# one-stage-full-wave-cockcroft-walton.net
KiCad netlist of a schematic drawn in EAGLE
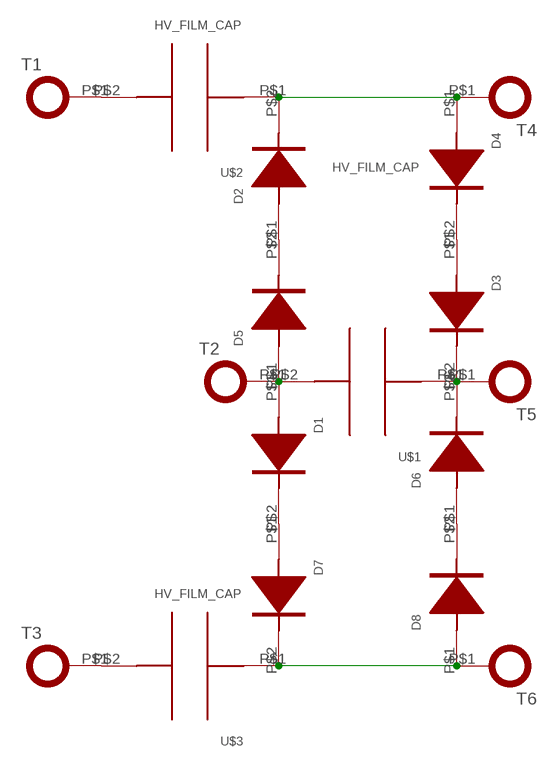
[diagram p0: schematic, sheet 1]

(export (version "E")
  (design (tool "Eeschema 10.0.6"))
  (components
    (comp (ref "D1")
      (value "DIODE_14MM")
      (footprint "eagle-import:DIODE_14")
      (libsource (lib "eagle-import") (part "DIODE_14MM"))
    )
    (comp (ref "D2")
      (value "DIODE_14MM")
      (footprint "eagle-import:DIODE_14")
      (libsource (lib "eagle-import") (part "DIODE_14MM"))
    )
    (comp (ref "D3")
      (value "DIODE_14MM")
      (footprint "eagle-import:DIODE_14")
      (libsource (lib "eagle-import") (part "DIODE_14MM"))
    )
    (comp (ref "D4")
      (value "DIODE_14MM")
      (footprint "eagle-import:DIODE_14")
      (libsource (lib "eagle-import") (part "DIODE_14MM"))
    )
    (comp (ref "D5")
      (value "DIODE_14MM")
      (footprint "eagle-import:DIODE_14")
      (libsource (lib "eagle-import") (part "DIODE_14MM"))
    )
    (comp (ref "D6")
      (value "DIODE_14MM")
      (footprint "eagle-import:DIODE_14")
      (libsource (lib "eagle-import") (part "DIODE_14MM"))
    )
    (comp (ref "D7")
      (value "DIODE_14MM")
      (footprint "eagle-import:DIODE_14")
      (libsource (lib "eagle-import") (part "DIODE_14MM"))
    )
    (comp (ref "D8")
      (value "DIODE_14MM")
      (footprint "eagle-import:DIODE_14")
      (libsource (lib "eagle-import") (part "DIODE_14MM"))
    )
    (comp (ref "T1")
      (value "TERMINAL_M6")
      (footprint "eagle-import:LUG_SQUARE_M6")
      (libsource (lib "eagle-import") (part "TERMINAL_M6"))
    )
    (comp (ref "T2")
      (value "TERMINAL_M6")
      (footprint "eagle-import:LUG_SQUARE_M6")
      (libsource (lib "eagle-import") (part "TERMINAL_M6"))
    )
    (comp (ref "T3")
      (value "TERMINAL_M6")
      (footprint "eagle-import:LUG_SQUARE_M6")
      (libsource (lib "eagle-import") (part "TERMINAL_M6"))
    )
    (comp (ref "T4")
      (value "TERMINAL_M6")
      (footprint "eagle-import:LUG_SQUARE_M6")
      (libsource (lib "eagle-import") (part "TERMINAL_M6"))
    )
    (comp (ref "T5")
      (value "TERMINAL_M6")
      (footprint "eagle-import:LUG_SQUARE_M6")
      (libsource (lib "eagle-import") (part "TERMINAL_M6"))
    )
    (comp (ref "T6")
      (value "TERMINAL_M6")
      (footprint "eagle-import:LUG_SQUARE_M6")
      (libsource (lib "eagle-import") (part "TERMINAL_M6"))
    )
    (comp (ref "U$1")
      (value "HV_FILM_CAP")
      (footprint "eagle-import:HV_FILM_CAP")
      (libsource (lib "eagle-import") (part "HV_FILM_CAP"))
    )
    (comp (ref "U$2")
      (value "HV_FILM_CAP")
      (footprint "eagle-import:HV_FILM_CAP")
      (libsource (lib "eagle-import") (part "HV_FILM_CAP"))
    )
    (comp (ref "U$3")
      (value "HV_FILM_CAP")
      (footprint "eagle-import:HV_FILM_CAP")
      (libsource (lib "eagle-import") (part "HV_FILM_CAP"))
    )
  )
  (nets
    (net (code "1") (name "Net-(D1-ANODE)") (class "Default")
      (node (ref "D1") (pin "P$1") (pinfunction "ANODE_P$1") (pintype "passive"))
      (node (ref "D5") (pin "P$1") (pinfunction "ANODE_P$1") (pintype "passive"))
      (node (ref "T2") (pin "P$1") (pinfunction "P$1_P$1") (pintype "passive"))
      (node (ref "U$1") (pin "P$2") (pinfunction "P$2_P$2") (pintype "passive"))
    )
    (net (code "2") (name "Net-(D1-CATHODE)") (class "Default")
      (node (ref "D1") (pin "P$2") (pinfunction "CATHODE_P$2") (pintype "passive"))
      (node (ref "D7") (pin "P$1") (pinfunction "ANODE_P$1") (pintype "passive"))
    )
    (net (code "3") (name "Net-(D2-ANODE)") (class "Default")
      (node (ref "D2") (pin "P$1") (pinfunction "ANODE_P$1") (pintype "passive"))
      (node (ref "D5") (pin "P$2") (pinfunction "CATHODE_P$2") (pintype "passive"))
    )
    (net (code "4") (name "Net-(D2-CATHODE)") (class "Default")
      (node (ref "D2") (pin "P$2") (pinfunction "CATHODE_P$2") (pintype "passive"))
      (node (ref "D4") (pin "P$1") (pinfunction "ANODE_P$1") (pintype "passive"))
      (node (ref "T4") (pin "P$1") (pinfunction "P$1_P$1") (pintype "passive"))
      (node (ref "U$2") (pin "P$1") (pinfunction "P$1_P$1") (pintype "passive"))
    )
    (net (code "5") (name "Net-(D3-ANODE)") (class "Default")
      (node (ref "D3") (pin "P$1") (pinfunction "ANODE_P$1") (pintype "passive"))
      (node (ref "D4") (pin "P$2") (pinfunction "CATHODE_P$2") (pintype "passive"))
    )
    (net (code "6") (name "Net-(D3-CATHODE)") (class "Default")
      (node (ref "D3") (pin "P$2") (pinfunction "CATHODE_P$2") (pintype "passive"))
      (node (ref "D6") (pin "P$2") (pinfunction "CATHODE_P$2") (pintype "passive"))
      (node (ref "T5") (pin "P$1") (pinfunction "P$1_P$1") (pintype "passive"))
      (node (ref "U$1") (pin "P$1") (pinfunction "P$1_P$1") (pintype "passive"))
    )
    (net (code "7") (name "Net-(D6-ANODE)") (class "Default")
      (node (ref "D6") (pin "P$1") (pinfunction "ANODE_P$1") (pintype "passive"))
      (node (ref "D8") (pin "P$2") (pinfunction "CATHODE_P$2") (pintype "passive"))
    )
    (net (code "8") (name "Net-(D7-CATHODE)") (class "Default")
      (node (ref "D7") (pin "P$2") (pinfunction "CATHODE_P$2") (pintype "passive"))
      (node (ref "D8") (pin "P$1") (pinfunction "ANODE_P$1") (pintype "passive"))
      (node (ref "T6") (pin "P$1") (pinfunction "P$1_P$1") (pintype "passive"))
      (node (ref "U$3") (pin "P$1") (pinfunction "P$1_P$1") (pintype "passive"))
    )
    (net (code "9") (name "Net-(T1-PadP$1)") (class "Default")
      (node (ref "T1") (pin "P$1") (pinfunction "P$1_P$1") (pintype "passive"))
      (node (ref "U$2") (pin "P$2") (pinfunction "P$2_P$2") (pintype "passive"))
    )
    (net (code "10") (name "Net-(T3-PadP$1)") (class "Default")
      (node (ref "T3") (pin "P$1") (pinfunction "P$1_P$1") (pintype "passive"))
      (node (ref "U$3") (pin "P$2") (pinfunction "P$2_P$2") (pintype "passive"))
    )
  )
)
